# interface_dac_sma_feedback_2PS_ADC_detec.net
KiCad netlist of a schematic drawn in EAGLE
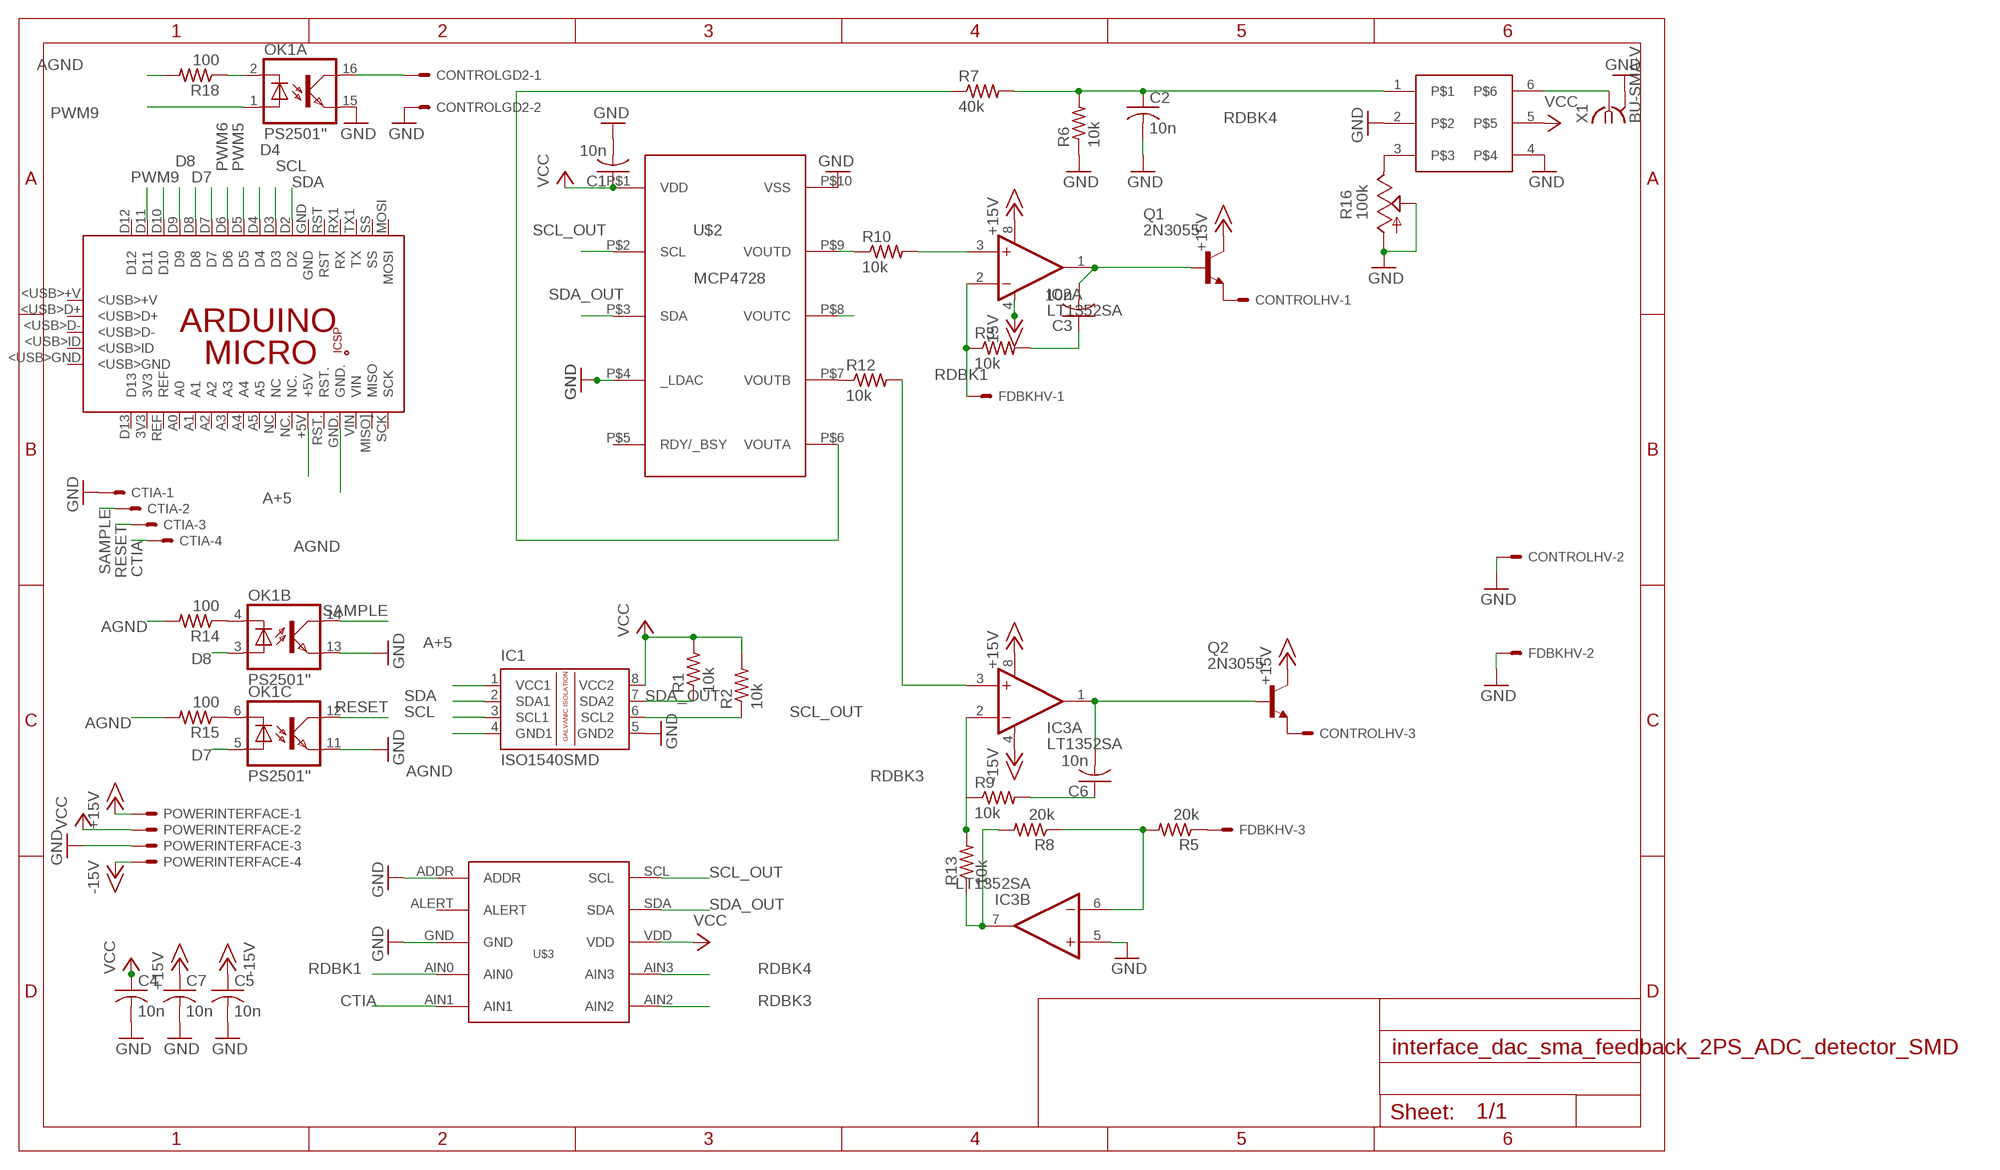
[diagram p0: schematic, sheet 1]

(export (version "E")
  (design (tool "Eeschema 10.0.6"))
  (components
    (comp (ref "C1")
      (value "10n")
      (footprint "eagle-import:C0805")
      (libsource (lib "eagle-import") (part "C-USC0805"))
    )
    (comp (ref "C2")
      (value "10n")
      (footprint "eagle-import:C0805")
      (libsource (lib "eagle-import") (part "resistor_C-USC0805"))
    )
    (comp (ref "C3")
      (value "10n")
      (footprint "eagle-import:C0805")
      (libsource (lib "eagle-import") (part "resistor_C-USC0805"))
    )
    (comp (ref "C4")
      (value "10n")
      (footprint "eagle-import:C0805")
      (libsource (lib "eagle-import") (part "resistor_C-USC0805"))
    )
    (comp (ref "C5")
      (value "10n")
      (footprint "eagle-import:C0805")
      (libsource (lib "eagle-import") (part "resistor_C-USC0805"))
    )
    (comp (ref "C6")
      (value "10n")
      (footprint "eagle-import:C0805")
      (libsource (lib "eagle-import") (part "resistor_C-USC0805"))
    )
    (comp (ref "C7")
      (value "10n")
      (footprint "eagle-import:C0805")
      (libsource (lib "eagle-import") (part "resistor_C-USC0805"))
    )
    (comp (ref "CONTROLGD2")
      (value "KK-156-2")
      (footprint "eagle-import:KK-156-2")
      (libsource (lib "eagle-import") (part "KK-156-2"))
    )
    (comp (ref "CONTROLHV")
      (value "KK-156-3")
      (footprint "eagle-import:KK-156-3")
      (libsource (lib "eagle-import") (part "KK-156-3"))
    )
    (comp (ref "CTIA")
      (value "KK-156-4")
      (footprint "eagle-import:KK-156-4")
      (libsource (lib "eagle-import") (part "KK-156-4"))
    )
    (comp (ref "FDBKHV")
      (value "KK-156-3")
      (footprint "eagle-import:KK-156-3")
      (libsource (lib "eagle-import") (part "KK-156-3"))
    )
    (comp (ref "IC1")
      (value "ISO1540SMD")
      (footprint "eagle-import:SOIC8")
      (libsource (lib "eagle-import") (part "ISO1540SMD"))
    )
    (comp (ref "IC2")
      (value "LT1352SA")
      (footprint "eagle-import:SO08")
      (libsource (lib "eagle-import") (part "LT1352SA"))
    )
    (comp (ref "IC3")
      (value "LT1352SA")
      (footprint "eagle-import:SO08")
      (libsource (lib "eagle-import") (part "LT1352SA"))
    )
    (comp (ref "OK1")
      (value "PS2501\"")
      (footprint "eagle-import:DIL16")
      (libsource (lib "eagle-import") (part "PS2501{dblquote}"))
    )
    (comp (ref "PCB1")
      (value "ARDUINO_MICRO")
      (footprint "eagle-import:ARDUINO_MICRO")
      (libsource (lib "eagle-import") (part "ARDUINO_MICRO"))
    )
    (comp (ref "POWERINTERFACE")
      (value "KK-156-4")
      (footprint "eagle-import:KK-156-4")
      (libsource (lib "eagle-import") (part "KK-156-4"))
    )
    (comp (ref "Q1")
      (value "2N3055")
      (footprint "eagle-import:TO3")
      (libsource (lib "eagle-import") (part "2N3055"))
    )
    (comp (ref "Q2")
      (value "2N3055")
      (footprint "eagle-import:TO3")
      (libsource (lib "eagle-import") (part "2N3055"))
    )
    (comp (ref "R1")
      (value "10k")
      (footprint "eagle-import:R0805")
      (libsource (lib "eagle-import") (part "resistor_R-US_R0805"))
    )
    (comp (ref "R2")
      (value "10k")
      (footprint "eagle-import:R0805")
      (libsource (lib "eagle-import") (part "resistor_R-US_R0805"))
    )
    (comp (ref "R3")
      (value "10k")
      (footprint "eagle-import:R0805")
      (libsource (lib "eagle-import") (part "resistor_R-US_R0805"))
    )
    (comp (ref "R5")
      (value "20k")
      (footprint "eagle-import:R0805")
      (libsource (lib "eagle-import") (part "resistor_R-US_R0805"))
    )
    (comp (ref "R6")
      (value "10k")
      (footprint "eagle-import:R0805")
      (libsource (lib "eagle-import") (part "resistor_R-US_R0805"))
    )
    (comp (ref "R7")
      (value "40k")
      (footprint "eagle-import:R0805")
      (libsource (lib "eagle-import") (part "resistor_R-US_R0805"))
    )
    (comp (ref "R8")
      (value "20k")
      (footprint "eagle-import:R0805")
      (libsource (lib "eagle-import") (part "resistor_R-US_R0805"))
    )
    (comp (ref "R9")
      (value "10k")
      (footprint "eagle-import:R0805")
      (libsource (lib "eagle-import") (part "resistor_R-US_R0805"))
    )
    (comp (ref "R10")
      (value "10k")
      (footprint "eagle-import:R0805")
      (libsource (lib "eagle-import") (part "resistor_R-US_R0805"))
    )
    (comp (ref "R12")
      (value "10k")
      (footprint "eagle-import:R0805")
      (libsource (lib "eagle-import") (part "resistor_R-US_R0805"))
    )
    (comp (ref "R13")
      (value "10k")
      (footprint "eagle-import:R0805")
      (libsource (lib "eagle-import") (part "resistor_R-US_R0805"))
    )
    (comp (ref "R14")
      (value "100")
      (footprint "eagle-import:R0805")
      (libsource (lib "eagle-import") (part "R-US_R0805"))
    )
    (comp (ref "R15")
      (value "100")
      (footprint "eagle-import:R0805")
      (libsource (lib "eagle-import") (part "R-US_R0805"))
    )
    (comp (ref "R16")
      (value "100k")
      (footprint "eagle-import:SP19L")
      (libsource (lib "eagle-import") (part "TRIM_US-B90P"))
    )
    (comp (ref "R18")
      (value "100")
      (footprint "eagle-import:R0805")
      (libsource (lib "eagle-import") (part "R-US_R0805"))
    )
    (comp (ref "U$1")
      (value "LTC6992SMD")
      (footprint "eagle-import:SOT23-6")
      (libsource (lib "eagle-import") (part "LTC6992SMD"))
    )
    (comp (ref "U$2")
      (value "MCP4728")
      (footprint "eagle-import:MSOP-10")
      (libsource (lib "eagle-import") (part "MCP4728"))
    )
    (comp (ref "U$3")
      (value "ADS1015")
      (footprint "eagle-import:VSOP-10")
      (libsource (lib "eagle-import") (part "ADS1015"))
    )
    (comp (ref "X1")
      (value "BU-SMA-V")
      (footprint "eagle-import:BU-SMA-V")
      (libsource (lib "eagle-import") (part "BU-SMA-V"))
    )
  )
  (nets
    (net (code "1") (name "+15V") (class "Default")
      (node (ref "C7") (pin "1") (pinfunction "1_1") (pintype "passive"))
      (node (ref "IC2") (pin "8") (pinfunction "V+_8") (pintype "power_in"))
      (node (ref "IC3") (pin "8") (pinfunction "V+_8") (pintype "power_in"))
      (node (ref "POWERINTERFACE") (pin "1") (pinfunction "S_1") (pintype "passive"))
      (node (ref "Q1") (pin "C") (pinfunction "C_C") (pintype "passive"))
      (node (ref "Q1") (pin "C/") (pinfunction "C_C/") (pintype "passive"))
      (node (ref "Q2") (pin "C") (pinfunction "C_C") (pintype "passive"))
      (node (ref "Q2") (pin "C/") (pinfunction "C_C/") (pintype "passive"))
    )
    (net (code "2") (name "-15V") (class "Default")
      (node (ref "C5") (pin "1") (pinfunction "1_1") (pintype "passive"))
      (node (ref "IC2") (pin "4") (pinfunction "V-_4") (pintype "power_in"))
      (node (ref "IC3") (pin "4") (pinfunction "V-_4") (pintype "power_in"))
      (node (ref "POWERINTERFACE") (pin "4") (pinfunction "S_4") (pintype "passive"))
    )
    (net (code "3") (name "/A+5") (class "Default")
      (node (ref "IC1") (pin "1") (pinfunction "VCC1_1") (pintype "input"))
      (node (ref "PCB1") (pin "+5V") (pinfunction "+5V_+5V") (pintype "bidirectional"))
    )
    (net (code "4") (name "/AGND") (class "Default")
      (node (ref "IC1") (pin "4") (pinfunction "GND1_4") (pintype "input"))
      (node (ref "PCB1") (pin "GND.") (pinfunction "GND._GND.") (pintype "bidirectional"))
      (node (ref "R14") (pin "2") (pinfunction "2_2") (pintype "passive"))
      (node (ref "R15") (pin "2") (pinfunction "2_2") (pintype "passive"))
      (node (ref "R18") (pin "2") (pinfunction "2_2") (pintype "passive"))
    )
    (net (code "5") (name "/CTIA") (class "Default")
      (node (ref "CTIA") (pin "4") (pinfunction "S_4") (pintype "passive"))
      (node (ref "U$3") (pin "AIN1") (pinfunction "AIN1_AIN1") (pintype "bidirectional"))
    )
    (net (code "6") (name "/D4") (class "Default")
      (node (ref "PCB1") (pin "D4") (pinfunction "D4_D4") (pintype "bidirectional"))
    )
    (net (code "7") (name "/D7") (class "Default")
      (node (ref "OK1") (pin "5") (pinfunction "A_5") (pintype "passive"))
      (node (ref "PCB1") (pin "D7") (pinfunction "D7_D7") (pintype "bidirectional"))
    )
    (net (code "8") (name "/D8") (class "Default")
      (node (ref "OK1") (pin "3") (pinfunction "A_3") (pintype "passive"))
      (node (ref "PCB1") (pin "D8") (pinfunction "D8_D8") (pintype "bidirectional"))
    )
    (net (code "9") (name "/PWM5") (class "Default")
      (node (ref "PCB1") (pin "D5") (pinfunction "D5_D5") (pintype "bidirectional"))
    )
    (net (code "10") (name "/PWM6") (class "Default")
      (node (ref "PCB1") (pin "D6") (pinfunction "D6_D6") (pintype "bidirectional"))
    )
    (net (code "11") (name "/PWM9") (class "Default")
      (node (ref "OK1") (pin "1") (pinfunction "A_1") (pintype "passive"))
      (node (ref "PCB1") (pin "D9") (pinfunction "D9_D9") (pintype "bidirectional"))
    )
    (net (code "12") (name "/RDBK1") (class "Default")
      (node (ref "FDBKHV") (pin "1") (pinfunction "S_1") (pintype "passive"))
      (node (ref "IC2") (pin "2") (pinfunction "-IN_2") (pintype "input"))
      (node (ref "R3") (pin "1") (pinfunction "1_1") (pintype "passive"))
      (node (ref "U$3") (pin "AIN0") (pinfunction "AIN0_AIN0") (pintype "bidirectional"))
    )
    (net (code "13") (name "/RDBK3") (class "Default")
      (node (ref "IC3") (pin "2") (pinfunction "-IN_2") (pintype "input"))
      (node (ref "R13") (pin "2") (pinfunction "2_2") (pintype "passive"))
      (node (ref "R9") (pin "1") (pinfunction "1_1") (pintype "passive"))
      (node (ref "U$3") (pin "AIN2") (pinfunction "AIN2_AIN2") (pintype "bidirectional"))
    )
    (net (code "14") (name "/RDBK4") (class "Default")
      (node (ref "C2") (pin "1") (pinfunction "1_1") (pintype "passive"))
      (node (ref "R6") (pin "2") (pinfunction "2_2") (pintype "passive"))
      (node (ref "R7") (pin "2") (pinfunction "2_2") (pintype "passive"))
      (node (ref "U$1") (pin "1") (pinfunction "P$1_1") (pintype "bidirectional"))
      (node (ref "U$3") (pin "AIN3") (pinfunction "AIN3_AIN3") (pintype "bidirectional"))
    )
    (net (code "15") (name "/RESET") (class "Default")
      (node (ref "CTIA") (pin "3") (pinfunction "S_3") (pintype "passive"))
      (node (ref "OK1") (pin "12") (pinfunction "COL_12") (pintype "passive"))
    )
    (net (code "16") (name "/SAMPLE") (class "Default")
      (node (ref "CTIA") (pin "2") (pinfunction "S_2") (pintype "passive"))
      (node (ref "OK1") (pin "14") (pinfunction "COL_14") (pintype "passive"))
    )
    (net (code "17") (name "/SCL") (class "Default")
      (node (ref "IC1") (pin "3") (pinfunction "SCL1_3") (pintype "input"))
      (node (ref "PCB1") (pin "D3") (pinfunction "D3_D3") (pintype "bidirectional"))
    )
    (net (code "18") (name "/SCL_OUT") (class "Default")
      (node (ref "IC1") (pin "6") (pinfunction "SCL2_6") (pintype "input"))
      (node (ref "R2") (pin "1") (pinfunction "1_1") (pintype "passive"))
      (node (ref "U$2") (pin "P$2") (pinfunction "SCL_P$2") (pintype "bidirectional"))
      (node (ref "U$3") (pin "SCL") (pinfunction "SCL_SCL") (pintype "bidirectional"))
    )
    (net (code "19") (name "/SDA") (class "Default")
      (node (ref "IC1") (pin "2") (pinfunction "SDA1_2") (pintype "input"))
      (node (ref "PCB1") (pin "D2") (pinfunction "D2_D2") (pintype "bidirectional"))
    )
    (net (code "20") (name "/SDA_OUT") (class "Default")
      (node (ref "IC1") (pin "7") (pinfunction "SDA2_7") (pintype "input"))
      (node (ref "R1") (pin "1") (pinfunction "1_1") (pintype "passive"))
      (node (ref "U$2") (pin "P$3") (pinfunction "SDA_P$3") (pintype "bidirectional"))
      (node (ref "U$3") (pin "SDA") (pinfunction "SDA_SDA") (pintype "bidirectional"))
    )
    (net (code "21") (name "GND") (class "Default")
      (node (ref "C1") (pin "2") (pinfunction "2_2") (pintype "passive"))
      (node (ref "C2") (pin "2") (pinfunction "2_2") (pintype "passive"))
      (node (ref "C4") (pin "2") (pinfunction "2_2") (pintype "passive"))
      (node (ref "C5") (pin "2") (pinfunction "2_2") (pintype "passive"))
      (node (ref "C7") (pin "2") (pinfunction "2_2") (pintype "passive"))
      (node (ref "CONTROLGD2") (pin "2") (pinfunction "S_2") (pintype "passive"))
      (node (ref "CONTROLHV") (pin "2") (pinfunction "S_2") (pintype "passive"))
      (node (ref "CTIA") (pin "1") (pinfunction "S_1") (pintype "passive"))
      (node (ref "FDBKHV") (pin "2") (pinfunction "S_2") (pintype "passive"))
      (node (ref "IC1") (pin "5") (pinfunction "GND2_5") (pintype "input"))
      (node (ref "IC3") (pin "5") (pinfunction "+IN_5") (pintype "input"))
      (node (ref "OK1") (pin "11") (pinfunction "EMI_11") (pintype "passive"))
      (node (ref "OK1") (pin "13") (pinfunction "EMI_13") (pintype "passive"))
      (node (ref "OK1") (pin "15") (pinfunction "EMI_15") (pintype "passive"))
      (node (ref "POWERINTERFACE") (pin "3") (pinfunction "S_3") (pintype "passive"))
      (node (ref "R16") (pin "A") (pinfunction "A_A") (pintype "passive"))
      (node (ref "R16") (pin "S") (pinfunction "S_S") (pintype "passive"))
      (node (ref "R6") (pin "1") (pinfunction "1_1") (pintype "passive"))
      (node (ref "U$1") (pin "2") (pinfunction "P$2_2") (pintype "bidirectional"))
      (node (ref "U$1") (pin "4") (pinfunction "P$4_4") (pintype "bidirectional"))
      (node (ref "U$2") (pin "P$10") (pinfunction "VSS_P$10") (pintype "bidirectional"))
      (node (ref "U$2") (pin "P$4") (pinfunction "_LDAC_P$4") (pintype "bidirectional"))
      (node (ref "U$3") (pin "ADDR") (pinfunction "ADDR_ADDR") (pintype "bidirectional"))
      (node (ref "U$3") (pin "GND") (pinfunction "GND_GND") (pintype "bidirectional"))
      (node (ref "X1") (pin "2") (pinfunction "2_2") (pintype "passive"))
      (node (ref "X1") (pin "3") (pinfunction "2_3") (pintype "passive"))
      (node (ref "X1") (pin "4") (pinfunction "2_4") (pintype "passive"))
      (node (ref "X1") (pin "5") (pinfunction "2_5") (pintype "passive"))
    )
    (net (code "22") (name "Net-(C3-Pad1)") (class "Default")
      (node (ref "C3") (pin "1") (pinfunction "1_1") (pintype "passive"))
      (node (ref "R3") (pin "2") (pinfunction "2_2") (pintype "passive"))
    )
    (net (code "23") (name "Net-(C6-Pad1)") (class "Default")
      (node (ref "C6") (pin "1") (pinfunction "1_1") (pintype "passive"))
      (node (ref "R9") (pin "2") (pinfunction "2_2") (pintype "passive"))
    )
    (net (code "24") (name "Net-(CONTROLGD2A-S)") (class "Default")
      (node (ref "CONTROLGD2") (pin "1") (pinfunction "S_1") (pintype "passive"))
      (node (ref "OK1") (pin "16") (pinfunction "COL_16") (pintype "passive"))
    )
    (net (code "25") (name "Net-(CONTROLHVA-S)") (class "Default")
      (node (ref "CONTROLHV") (pin "1") (pinfunction "S_1") (pintype "passive"))
      (node (ref "Q1") (pin "E") (pinfunction "E_E") (pintype "passive"))
    )
    (net (code "26") (name "Net-(CONTROLHVC-S)") (class "Default")
      (node (ref "CONTROLHV") (pin "3") (pinfunction "S_3") (pintype "passive"))
      (node (ref "Q2") (pin "E") (pinfunction "E_E") (pintype "passive"))
    )
    (net (code "27") (name "Net-(FDBKHVC-S)") (class "Default")
      (node (ref "FDBKHV") (pin "3") (pinfunction "S_3") (pintype "passive"))
      (node (ref "R5") (pin "1") (pinfunction "1_1") (pintype "passive"))
    )
    (net (code "28") (name "Net-(IC2A-+IN)") (class "Default")
      (node (ref "IC2") (pin "3") (pinfunction "+IN_3") (pintype "input"))
      (node (ref "R10") (pin "2") (pinfunction "2_2") (pintype "passive"))
    )
    (net (code "29") (name "Net-(IC2A-OUT)") (class "Default")
      (node (ref "C3") (pin "2") (pinfunction "2_2") (pintype "passive"))
      (node (ref "IC2") (pin "1") (pinfunction "OUT_1") (pintype "output"))
      (node (ref "Q1") (pin "B") (pinfunction "B_B") (pintype "passive"))
    )
    (net (code "30") (name "Net-(IC3A-+IN)") (class "Default")
      (node (ref "IC3") (pin "3") (pinfunction "+IN_3") (pintype "input"))
      (node (ref "R12") (pin "2") (pinfunction "2_2") (pintype "passive"))
    )
    (net (code "31") (name "Net-(IC3A-OUT)") (class "Default")
      (node (ref "C6") (pin "2") (pinfunction "2_2") (pintype "passive"))
      (node (ref "IC3") (pin "1") (pinfunction "OUT_1") (pintype "output"))
      (node (ref "Q2") (pin "B") (pinfunction "B_B") (pintype "passive"))
    )
    (net (code "32") (name "Net-(IC3B--IN)") (class "Default")
      (node (ref "IC3") (pin "6") (pinfunction "-IN_6") (pintype "input"))
      (node (ref "R5") (pin "2") (pinfunction "2_2") (pintype "passive"))
      (node (ref "R8") (pin "1") (pinfunction "1_1") (pintype "passive"))
    )
    (net (code "33") (name "Net-(IC3B-OUT)") (class "Default")
      (node (ref "IC3") (pin "7") (pinfunction "OUT_7") (pintype "output"))
      (node (ref "R13") (pin "1") (pinfunction "1_1") (pintype "passive"))
      (node (ref "R8") (pin "2") (pinfunction "2_2") (pintype "passive"))
    )
    (net (code "34") (name "Net-(OK1A-C)") (class "Default")
      (node (ref "OK1") (pin "2") (pinfunction "C_2") (pintype "passive"))
      (node (ref "R18") (pin "1") (pinfunction "1_1") (pintype "passive"))
    )
    (net (code "35") (name "Net-(OK1B-C)") (class "Default")
      (node (ref "OK1") (pin "4") (pinfunction "C_4") (pintype "passive"))
      (node (ref "R14") (pin "1") (pinfunction "1_1") (pintype "passive"))
    )
    (net (code "36") (name "Net-(OK1C-C)") (class "Default")
      (node (ref "OK1") (pin "6") (pinfunction "C_6") (pintype "passive"))
      (node (ref "R15") (pin "1") (pinfunction "1_1") (pintype "passive"))
    )
    (net (code "37") (name "Net-(U$1-P$3)") (class "Default")
      (node (ref "R16") (pin "E") (pinfunction "E_E") (pintype "passive"))
      (node (ref "U$1") (pin "3") (pinfunction "P$3_3") (pintype "bidirectional"))
    )
    (net (code "38") (name "Net-(U$1-P$6)") (class "Default")
      (node (ref "U$1") (pin "6") (pinfunction "P$6_6") (pintype "bidirectional"))
      (node (ref "X1") (pin "1") (pinfunction "1_1") (pintype "passive"))
    )
    (net (code "39") (name "Net-(U$2-VOUTA)") (class "Default")
      (node (ref "R7") (pin "1") (pinfunction "1_1") (pintype "passive"))
      (node (ref "U$2") (pin "P$6") (pinfunction "VOUTA_P$6") (pintype "bidirectional"))
    )
    (net (code "40") (name "Net-(U$2-VOUTB)") (class "Default")
      (node (ref "R12") (pin "1") (pinfunction "1_1") (pintype "passive"))
      (node (ref "U$2") (pin "P$7") (pinfunction "VOUTB_P$7") (pintype "bidirectional"))
    )
    (net (code "41") (name "Net-(U$2-VOUTD)") (class "Default")
      (node (ref "R10") (pin "1") (pinfunction "1_1") (pintype "passive"))
      (node (ref "U$2") (pin "P$9") (pinfunction "VOUTD_P$9") (pintype "bidirectional"))
    )
    (net (code "42") (name "VCC") (class "Default")
      (node (ref "C1") (pin "1") (pinfunction "1_1") (pintype "passive"))
      (node (ref "C4") (pin "1") (pinfunction "1_1") (pintype "passive"))
      (node (ref "IC1") (pin "8") (pinfunction "VCC2_8") (pintype "input"))
      (node (ref "POWERINTERFACE") (pin "2") (pinfunction "S_2") (pintype "passive"))
      (node (ref "R1") (pin "2") (pinfunction "2_2") (pintype "passive"))
      (node (ref "R2") (pin "2") (pinfunction "2_2") (pintype "passive"))
      (node (ref "U$1") (pin "5") (pinfunction "P$5_5") (pintype "bidirectional"))
      (node (ref "U$2") (pin "P$1") (pinfunction "VDD_P$1") (pintype "bidirectional"))
      (node (ref "U$3") (pin "VDD") (pinfunction "VDD_VDD") (pintype "bidirectional"))
    )
    (net (code "43") (name "unconnected-(PCB1-MISO-PadMISO])") (class "Default")
      (node (ref "PCB1") (pin "MISO]") (pinfunction "MISO_MISO]") (pintype "bidirectional"))
    )
    (net (code "44") (name "unconnected-(PCB1-Pad3V3)") (class "Default")
      (node (ref "PCB1") (pin "3V3") (pinfunction "3V3_3V3") (pintype "bidirectional"))
    )
    (net (code "45") (name "unconnected-(PCB1-Pad5V)") (class "Default")
      (node (ref "PCB1") (pin "5V") (pinfunction "5V_5V") (pintype "bidirectional"))
    )
    (net (code "46") (name "unconnected-(PCB1-Pad<USB>+V)") (class "Default")
      (node (ref "PCB1") (pin "<USB>+V") (pinfunction "<USB>+V_<USB>+V") (pintype "bidirectional"))
    )
    (net (code "47") (name "unconnected-(PCB1-Pad<USB>D+)") (class "Default")
      (node (ref "PCB1") (pin "<USB>D+") (pinfunction "<USB>D+_<USB>D+") (pintype "bidirectional"))
    )
    (net (code "48") (name "unconnected-(PCB1-Pad<USB>D-)") (class "Default")
      (node (ref "PCB1") (pin "<USB>D-") (pinfunction "<USB>D-_<USB>D-") (pintype "bidirectional"))
    )
    (net (code "49") (name "unconnected-(PCB1-Pad<USB>GND)") (class "Default")
      (node (ref "PCB1") (pin "<USB>GND") (pinfunction "<USB>GND_<USB>GND") (pintype "bidirectional"))
    )
    (net (code "50") (name "unconnected-(PCB1-Pad<USB>ID)") (class "Default")
      (node (ref "PCB1") (pin "<USB>ID") (pinfunction "<USB>ID_<USB>ID") (pintype "bidirectional"))
    )
    (net (code "51") (name "unconnected-(PCB1-PadA0)") (class "Default")
      (node (ref "PCB1") (pin "A0") (pinfunction "A0_A0") (pintype "bidirectional"))
    )
    (net (code "52") (name "unconnected-(PCB1-PadA1)") (class "Default")
      (node (ref "PCB1") (pin "A1") (pinfunction "A1_A1") (pintype "bidirectional"))
    )
    (net (code "53") (name "unconnected-(PCB1-PadA2)") (class "Default")
      (node (ref "PCB1") (pin "A2") (pinfunction "A2_A2") (pintype "bidirectional"))
    )
    (net (code "54") (name "unconnected-(PCB1-PadA3)") (class "Default")
      (node (ref "PCB1") (pin "A3") (pinfunction "A3_A3") (pintype "bidirectional"))
    )
    (net (code "55") (name "unconnected-(PCB1-PadA4)") (class "Default")
      (node (ref "PCB1") (pin "A4") (pinfunction "A4_A4") (pintype "bidirectional"))
    )
    (net (code "56") (name "unconnected-(PCB1-PadA5)") (class "Default")
      (node (ref "PCB1") (pin "A5") (pinfunction "A5_A5") (pintype "bidirectional"))
    )
    (net (code "57") (name "unconnected-(PCB1-PadD10)") (class "Default")
      (node (ref "PCB1") (pin "D10") (pinfunction "D10_D10") (pintype "bidirectional"))
    )
    (net (code "58") (name "unconnected-(PCB1-PadD11)") (class "Default")
      (node (ref "PCB1") (pin "D11") (pinfunction "D11_D11") (pintype "bidirectional"))
    )
    (net (code "59") (name "unconnected-(PCB1-PadD12)") (class "Default")
      (node (ref "PCB1") (pin "D12") (pinfunction "D12_D12") (pintype "bidirectional"))
    )
    (net (code "60") (name "unconnected-(PCB1-PadD13)") (class "Default")
      (node (ref "PCB1") (pin "D13") (pinfunction "D13_D13") (pintype "bidirectional"))
    )
    (net (code "61") (name "unconnected-(PCB1-PadGND)") (class "Default")
      (node (ref "PCB1") (pin "GND") (pinfunction "GND_GND") (pintype "bidirectional"))
    )
    (net (code "62") (name "unconnected-(PCB1-PadGND_)") (class "Default")
      (node (ref "PCB1") (pin "GND_") (pinfunction "GND__GND_") (pintype "bidirectional"))
    )
    (net (code "63") (name "unconnected-(PCB1-PadMISO.)") (class "Default")
      (node (ref "PCB1") (pin "MISO.") (pinfunction "MISO._MISO.") (pintype "bidirectional"))
    )
    (net (code "64") (name "unconnected-(PCB1-PadMOSI)") (class "Default")
      (node (ref "PCB1") (pin "MOSI") (pinfunction "MOSI_MOSI") (pintype "bidirectional"))
    )
    (net (code "65") (name "unconnected-(PCB1-PadMOSI.)") (class "Default")
      (node (ref "PCB1") (pin "MOSI.") (pinfunction "MOSI._MOSI.") (pintype "bidirectional"))
    )
    (net (code "66") (name "unconnected-(PCB1-PadNC)") (class "Default")
      (node (ref "PCB1") (pin "NC") (pinfunction "NC_NC") (pintype "bidirectional"))
    )
    (net (code "67") (name "unconnected-(PCB1-PadNC.)") (class "Default")
      (node (ref "PCB1") (pin "NC.") (pinfunction "NC._NC.") (pintype "bidirectional"))
    )
    (net (code "68") (name "unconnected-(PCB1-PadREF)") (class "Default")
      (node (ref "PCB1") (pin "REF") (pinfunction "REF_REF") (pintype "bidirectional"))
    )
    (net (code "69") (name "unconnected-(PCB1-PadRESET..)") (class "Default")
      (node (ref "PCB1") (pin "RESET..") (pinfunction "RESET.._RESET..") (pintype "bidirectional"))
    )
    (net (code "70") (name "unconnected-(PCB1-PadRST)") (class "Default")
      (node (ref "PCB1") (pin "RST") (pinfunction "RST_RST") (pintype "bidirectional"))
    )
    (net (code "71") (name "unconnected-(PCB1-PadRST.)") (class "Default")
      (node (ref "PCB1") (pin "RST.") (pinfunction "RST._RST.") (pintype "bidirectional"))
    )
    (net (code "72") (name "unconnected-(PCB1-PadSCK)") (class "Default")
      (node (ref "PCB1") (pin "SCK") (pinfunction "SCK_SCK") (pintype "bidirectional"))
    )
    (net (code "73") (name "unconnected-(PCB1-PadSCK.)") (class "Default")
      (node (ref "PCB1") (pin "SCK.") (pinfunction "SCK._SCK.") (pintype "bidirectional"))
    )
    (net (code "74") (name "unconnected-(PCB1-PadSS)") (class "Default")
      (node (ref "PCB1") (pin "SS") (pinfunction "SS_SS") (pintype "bidirectional"))
    )
    (net (code "75") (name "unconnected-(PCB1-PadVIN)") (class "Default")
      (node (ref "PCB1") (pin "VIN") (pinfunction "VIN_VIN") (pintype "bidirectional"))
    )
    (net (code "76") (name "unconnected-(PCB1-RX-PadRX1)") (class "Default")
      (node (ref "PCB1") (pin "RX1") (pinfunction "RX_RX1") (pintype "bidirectional"))
    )
    (net (code "77") (name "unconnected-(PCB1-TX-PadTX1)") (class "Default")
      (node (ref "PCB1") (pin "TX1") (pinfunction "TX_TX1") (pintype "bidirectional"))
    )
    (net (code "78") (name "unconnected-(U$2-RDY{slash}_BSY-PadP$5)") (class "Default")
      (node (ref "U$2") (pin "P$5") (pinfunction "RDY/_BSY_P$5") (pintype "bidirectional"))
    )
    (net (code "79") (name "unconnected-(U$2-VOUTC-PadP$8)") (class "Default")
      (node (ref "U$2") (pin "P$8") (pinfunction "VOUTC_P$8") (pintype "bidirectional"))
    )
    (net (code "80") (name "unconnected-(U$3-PadALERT)") (class "Default")
      (node (ref "U$3") (pin "ALERT") (pinfunction "ALERT_ALERT") (pintype "bidirectional"))
    )
  )
)
